# DS18B20.net
KiCad netlist of a schematic drawn in Altium Designer
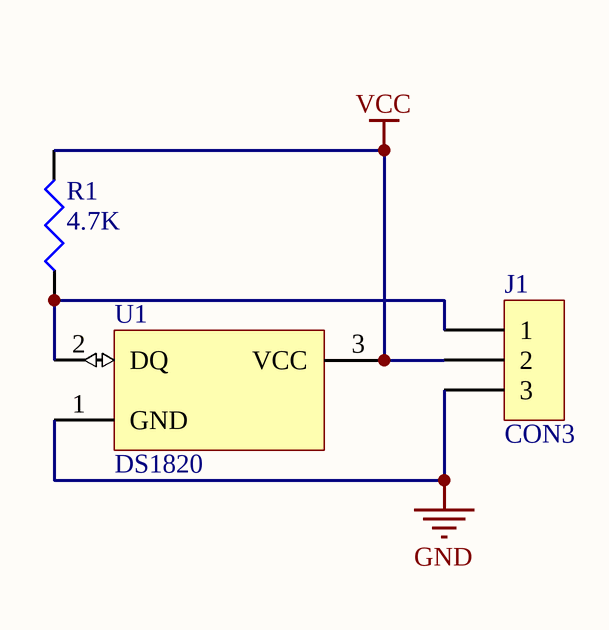
[diagram p0: DS18B20.SchDoc]

(export (version "E")
  (design (tool "Eeschema 10.0.6"))
  (components
    (comp (ref "J1")
      (value "CON3")
      (footprint "DevModule")
      (description "Connector")
      (libsource (lib "CON系列") (part "CON3"))
    )
    (comp (ref "R1") (value "4.7K") (footprint "6-0805_N") (libsource (lib "电阻器") (part "RES1_1")))
    (comp (ref "U1")
      (value "DS1820")
      (footprint "PR35")
      (description "1-Wire Digital Thermometer")
      (fields (field (name "PUBLISHER") "Altium Limited"))
      (libsource (lib "Dallas Sensor Temperature Sensor") (part "DS1820"))
    )
  )
  (nets
    (net (code "1") (name "GND") (class "Default")
      (node (ref "J1") (pin "3") (pinfunction "3_3") (pintype "passive"))
      (node (ref "U1") (pin "1") (pinfunction "GND_1") (pintype "power_in"))
    )
    (net (code "2") (name "Net-(U1-DQ)") (class "Default")
      (node (ref "J1") (pin "1") (pinfunction "1_1") (pintype "passive"))
      (node (ref "R1") (pin "1") (pinfunction "1_1") (pintype "passive"))
      (node (ref "U1") (pin "2") (pinfunction "DQ_2") (pintype "bidirectional"))
    )
    (net (code "3") (name "VCC") (class "Default")
      (node (ref "J1") (pin "2") (pinfunction "2_2") (pintype "passive"))
      (node (ref "R1") (pin "2") (pinfunction "2_2") (pintype "passive"))
      (node (ref "U1") (pin "3") (pinfunction "VCC_3") (pintype "power_in"))
    )
  )
)
